# control.net
KiCad netlist of a schematic drawn in Altium Designer
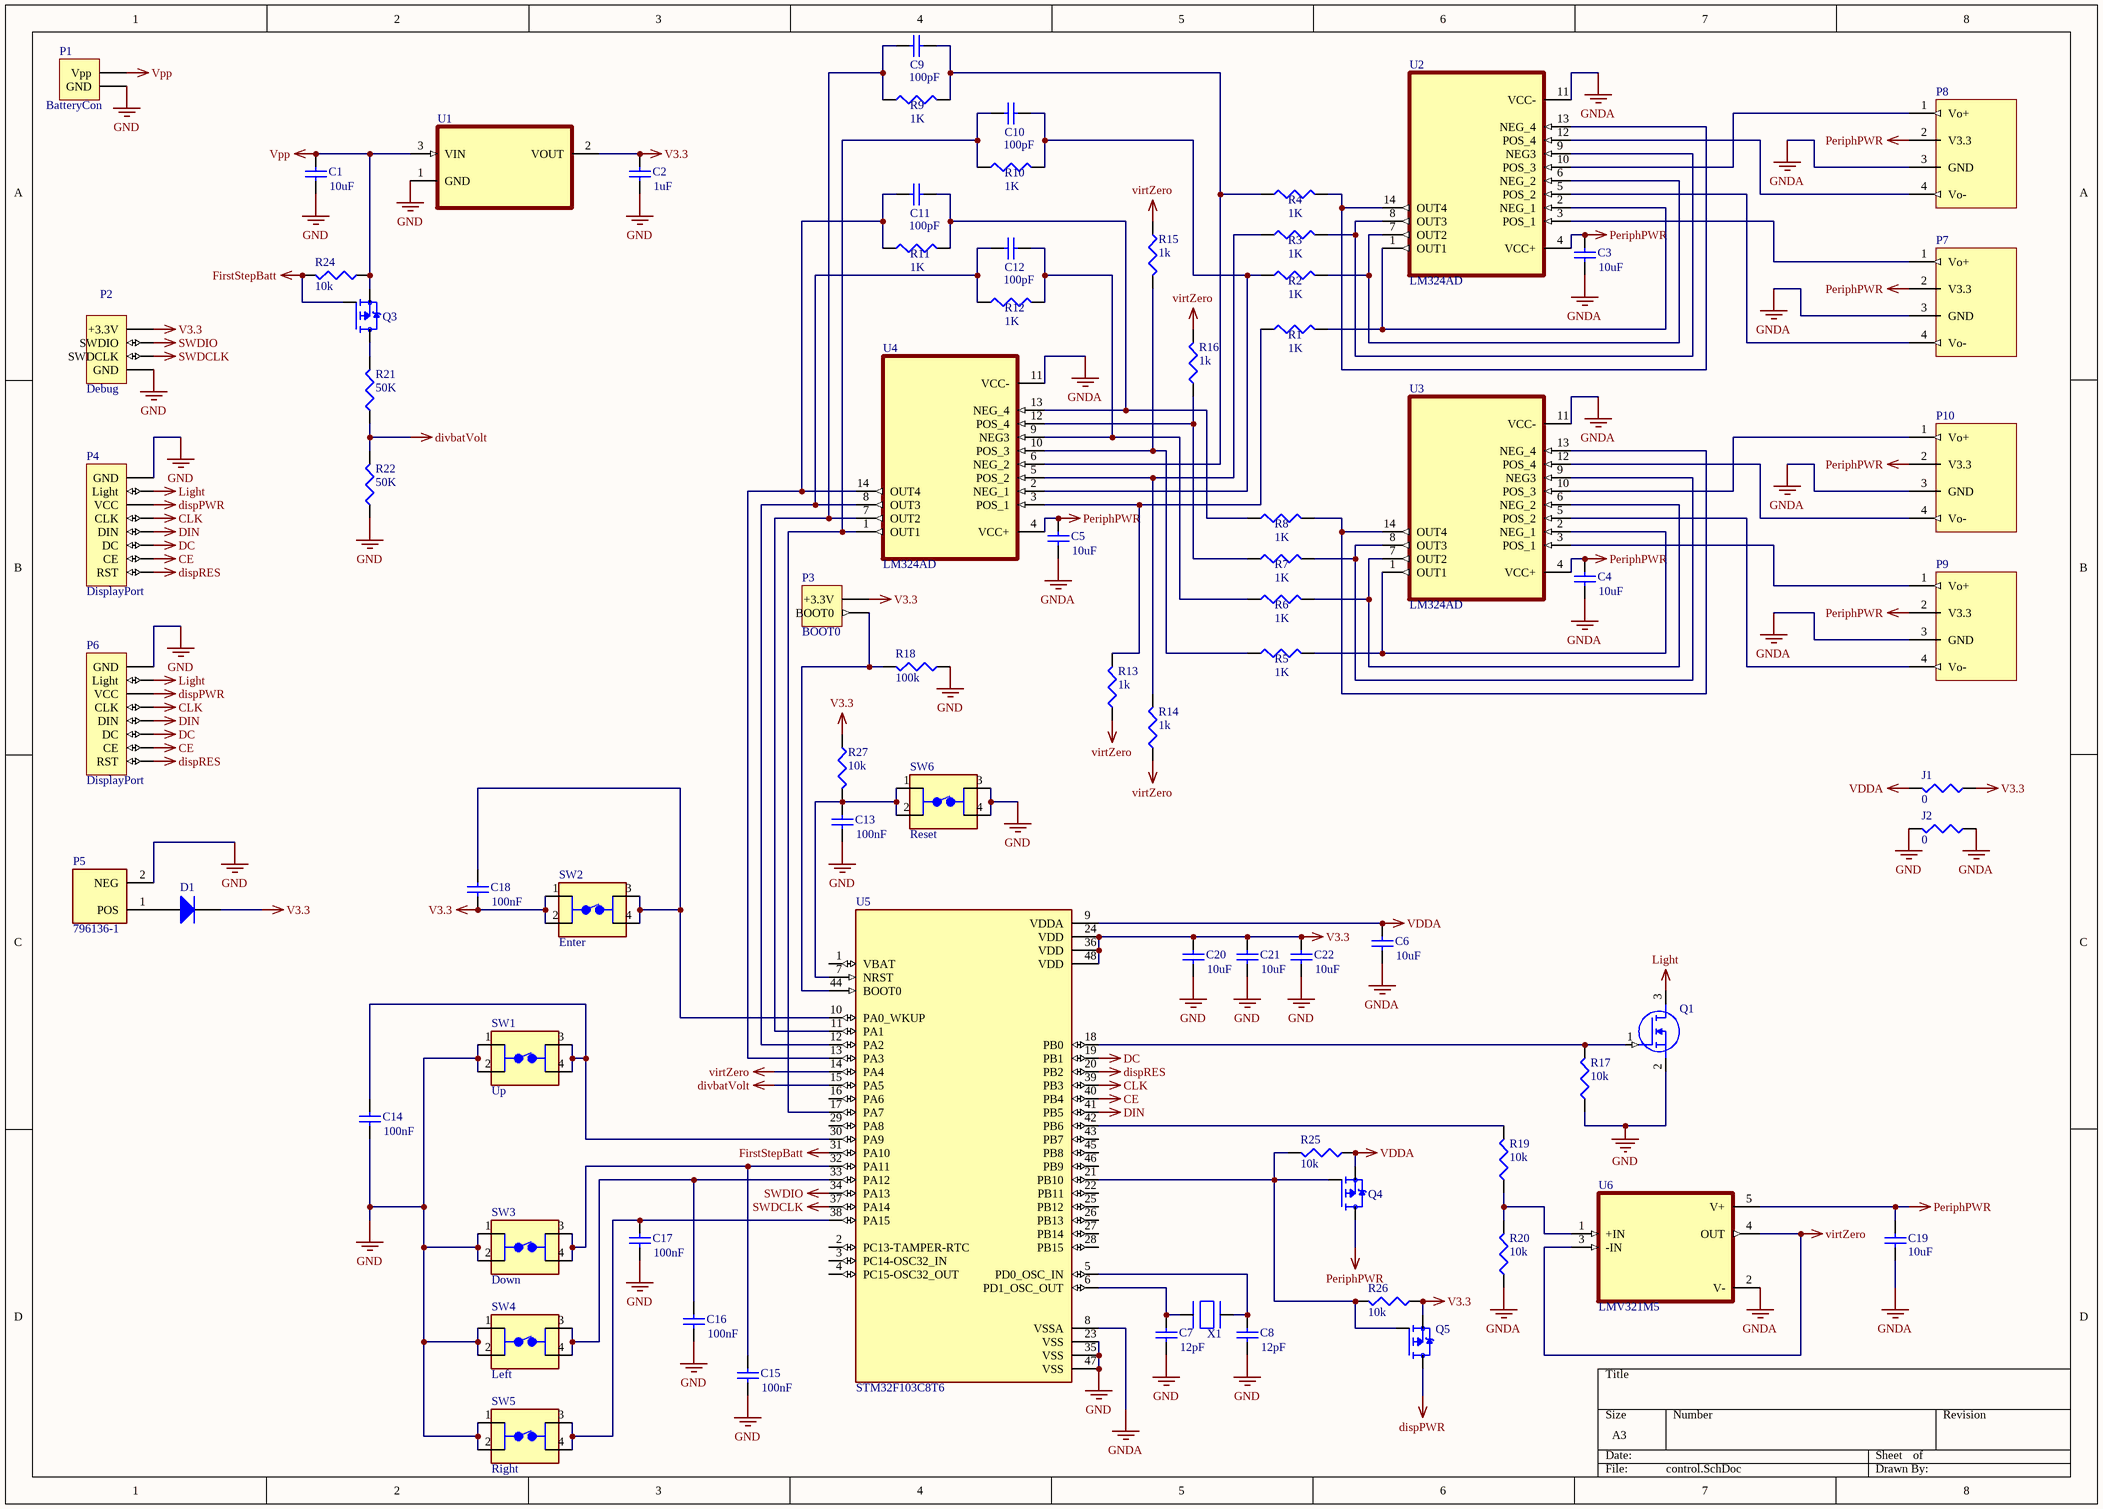
[diagram p0: control.SchDoc]

(export (version "E")
  (design (tool "Eeschema 10.0.6"))
  (components
    (comp (ref "C1")
      (value "10uF")
      (footprint "C1206")
      (description "Capacitor (Semiconductor SIM Model)")
      (fields (field (name "Comment") "Cap Semi") (field (name "PUBLISHER") "Altium Limited"))
      (libsource (lib "Miscellaneous Devices") (part "Cap Semi"))
    )
    (comp (ref "C2")
      (value "1uF")
      (footprint "C1206")
      (description "Capacitor (Semiconductor SIM Model)")
      (fields (field (name "Comment") "Cap Semi") (field (name "PUBLISHER") "Altium Limited"))
      (libsource (lib "Miscellaneous Devices") (part "Cap Semi"))
    )
    (comp (ref "C3")
      (value "10uF")
      (footprint "C1206")
      (description "Capacitor (Semiconductor SIM Model)")
      (fields (field (name "Comment") "Cap Semi") (field (name "PUBLISHER") "Altium Limited"))
      (libsource (lib "Miscellaneous Devices") (part "Cap Semi"))
    )
    (comp (ref "C4")
      (value "10uF")
      (footprint "C1206")
      (description "Capacitor (Semiconductor SIM Model)")
      (fields (field (name "Comment") "Cap Semi") (field (name "PUBLISHER") "Altium Limited"))
      (libsource (lib "Miscellaneous Devices") (part "Cap Semi"))
    )
    (comp (ref "C5")
      (value "10uF")
      (footprint "C1206")
      (description "Capacitor (Semiconductor SIM Model)")
      (fields (field (name "Comment") "Cap Semi") (field (name "PUBLISHER") "Altium Limited"))
      (libsource (lib "Miscellaneous Devices") (part "Cap Semi"))
    )
    (comp (ref "C6")
      (value "10uF")
      (footprint "C1206")
      (description "Capacitor (Semiconductor SIM Model)")
      (fields (field (name "Comment") "Cap Semi") (field (name "PUBLISHER") "Altium Limited"))
      (libsource (lib "Miscellaneous Devices") (part "Cap Semi"))
    )
    (comp (ref "C7")
      (value "12pF")
      (footprint "C1206")
      (description "Capacitor (Semiconductor SIM Model)")
      (fields (field (name "Comment") "Cap Semi") (field (name "PUBLISHER") "Altium Limited"))
      (libsource (lib "Miscellaneous Devices") (part "Cap Semi"))
    )
    (comp (ref "C8")
      (value "12pF")
      (footprint "C1206")
      (description "Capacitor (Semiconductor SIM Model)")
      (fields (field (name "Comment") "Cap Semi") (field (name "PUBLISHER") "Altium Limited"))
      (libsource (lib "Miscellaneous Devices") (part "Cap Semi"))
    )
    (comp (ref "C9")
      (value "100pF")
      (footprint "C1206")
      (description "Capacitor (Semiconductor SIM Model)")
      (fields (field (name "Comment") "Cap Semi") (field (name "PUBLISHER") "Altium Limited"))
      (libsource (lib "Miscellaneous Devices") (part "Cap Semi"))
    )
    (comp (ref "C10")
      (value "100pF")
      (footprint "C1206")
      (description "Capacitor (Semiconductor SIM Model)")
      (fields (field (name "Comment") "Cap Semi") (field (name "PUBLISHER") "Altium Limited"))
      (libsource (lib "Miscellaneous Devices") (part "Cap Semi"))
    )
    (comp (ref "C11")
      (value "100pF")
      (footprint "C1206")
      (description "Capacitor (Semiconductor SIM Model)")
      (fields (field (name "Comment") "Cap Semi") (field (name "PUBLISHER") "Altium Limited"))
      (libsource (lib "Miscellaneous Devices") (part "Cap Semi"))
    )
    (comp (ref "C12")
      (value "100pF")
      (footprint "C1206")
      (description "Capacitor (Semiconductor SIM Model)")
      (fields (field (name "Comment") "Cap Semi") (field (name "PUBLISHER") "Altium Limited"))
      (libsource (lib "Miscellaneous Devices") (part "Cap Semi"))
    )
    (comp (ref "C13")
      (value "100nF")
      (footprint "C1206")
      (description "Capacitor (Semiconductor SIM Model)")
      (fields (field (name "Comment") "Cap Semi") (field (name "PUBLISHER") "Altium Limited"))
      (libsource (lib "Miscellaneous Devices") (part "Cap Semi"))
    )
    (comp (ref "C14")
      (value "100nF")
      (footprint "C1206")
      (description "Capacitor (Semiconductor SIM Model)")
      (fields (field (name "Comment") "Cap Semi") (field (name "PUBLISHER") "Altium Limited"))
      (libsource (lib "Miscellaneous Devices") (part "Cap Semi"))
    )
    (comp (ref "C15")
      (value "100nF")
      (footprint "C1206")
      (description "Capacitor (Semiconductor SIM Model)")
      (fields (field (name "Comment") "Cap Semi") (field (name "PUBLISHER") "Altium Limited"))
      (libsource (lib "Miscellaneous Devices") (part "Cap Semi"))
    )
    (comp (ref "C16")
      (value "100nF")
      (footprint "C1206")
      (description "Capacitor (Semiconductor SIM Model)")
      (fields (field (name "Comment") "Cap Semi") (field (name "PUBLISHER") "Altium Limited"))
      (libsource (lib "Miscellaneous Devices") (part "Cap Semi"))
    )
    (comp (ref "C17")
      (value "100nF")
      (footprint "C1206")
      (description "Capacitor (Semiconductor SIM Model)")
      (fields (field (name "Comment") "Cap Semi") (field (name "PUBLISHER") "Altium Limited"))
      (libsource (lib "Miscellaneous Devices") (part "Cap Semi"))
    )
    (comp (ref "C18")
      (value "100nF")
      (footprint "C1206")
      (description "Capacitor (Semiconductor SIM Model)")
      (fields (field (name "Comment") "Cap Semi") (field (name "PUBLISHER") "Altium Limited"))
      (libsource (lib "Miscellaneous Devices") (part "Cap Semi"))
    )
    (comp (ref "C19")
      (value "10uF")
      (footprint "C1206")
      (description "Capacitor (Semiconductor SIM Model)")
      (fields (field (name "Comment") "Cap Semi") (field (name "PUBLISHER") "Altium Limited"))
      (libsource (lib "Miscellaneous Devices") (part "Cap Semi"))
    )
    (comp (ref "C20")
      (value "10uF")
      (footprint "C1206")
      (description "Capacitor (Semiconductor SIM Model)")
      (fields (field (name "Comment") "Cap Semi") (field (name "PUBLISHER") "Altium Limited"))
      (libsource (lib "Miscellaneous Devices") (part "Cap Semi"))
    )
    (comp (ref "C21")
      (value "10uF")
      (footprint "C1206")
      (description "Capacitor (Semiconductor SIM Model)")
      (fields (field (name "Comment") "Cap Semi") (field (name "PUBLISHER") "Altium Limited"))
      (libsource (lib "Miscellaneous Devices") (part "Cap Semi"))
    )
    (comp (ref "C22")
      (value "10uF")
      (footprint "C1206")
      (description "Capacitor (Semiconductor SIM Model)")
      (fields (field (name "Comment") "Cap Semi") (field (name "PUBLISHER") "Altium Limited"))
      (libsource (lib "Miscellaneous Devices") (part "Cap Semi"))
    )
    (comp (ref "D1")
      (value "Diode")
      (footprint "SMC")
      (description "Default Diode")
      (fields (field (name "PUBLISHER") "Altium Limited"))
      (libsource (lib "Miscellaneous Devices") (part "Diode"))
    )
    (comp (ref "J1")
      (value "0")
      (footprint "14-1210")
      (description "Resistor")
      (fields (field (name "Comment") "Res3") (field (name "PUBLISHER") "Altium Limited"))
      (libsource (lib "Miscellaneous Devices") (part "Res3"))
    )
    (comp (ref "J2")
      (value "0")
      (footprint "14-1210")
      (description "Resistor")
      (fields (field (name "Comment") "Res3") (field (name "PUBLISHER") "Altium Limited"))
      (libsource (lib "Miscellaneous Devices") (part "Res3"))
    )
    (comp (ref "P1")
      (value "BatteryCon")
      (footprint "HDR1X2")
      (description "Header, 2-Pin")
      (fields (field (name "PUBLISHER") "Altium Limited"))
      (libsource (lib "Miscellaneous Connectors") (part "Header 2"))
    )
    (comp (ref "P2")
      (value "Debug")
      (footprint "HDR1X4")
      (description "Header, 4-Pin")
      (fields (field (name "PUBLISHER") "Altium Limited"))
      (libsource (lib "Miscellaneous Connectors") (part "Header 4"))
    )
    (comp (ref "P3")
      (value "BOOT0")
      (footprint "HDR1X2")
      (description "Header, 2-Pin")
      (fields (field (name "PUBLISHER") "Altium Limited"))
      (libsource (lib "Miscellaneous Connectors") (part "Header 2"))
    )
    (comp (ref "P4")
      (value "DisplayPort")
      (footprint "HDR1X8")
      (description "Header, 8-Pin")
      (fields (field (name "PUBLISHER") "Altium Limited"))
      (libsource (lib "Miscellaneous Connectors") (part "Header 8"))
    )
    (comp (ref "P5")
      (value "796136-1")
      (footprint "TE_796136-1")
      (fields (field (name "MF") "TE Connectivity"))
      (libsource (lib "796136-1") (part "796136-1"))
    )
    (comp (ref "P6")
      (value "DisplayPort")
      (footprint "HDR1X8")
      (description "Header, 8-Pin")
      (fields (field (name "PUBLISHER") "Altium Limited"))
      (libsource (lib "Miscellaneous Connectors") (part "Header 8"))
    )
    (comp (ref "P7") (value "Conn") (footprint "ConnFoot") (libsource (lib "ConnLib") (part "ConnectorSMD")))
    (comp (ref "P8") (value "Conn") (footprint "ConnFoot") (libsource (lib "ConnLib") (part "ConnectorSMD")))
    (comp (ref "P9") (value "Conn") (footprint "ConnFoot") (libsource (lib "ConnLib") (part "ConnectorSMD")))
    (comp (ref "P10") (value "Conn") (footprint "ConnFoot") (libsource (lib "ConnLib") (part "ConnectorSMD")))
    (comp (ref "Q1")
      (value "IRLML0030TRPBF")
      (footprint "SOT23_L")
      (description "N-Channel 30V 5.3A _Ta_ 1.3W _Ta_ Surface Mount Micro3â„¢/SOT-23")
      (fields (field (name "MF") "Infineon Technologies"))
      (libsource (lib "IRLML0030TRPBF") (part "IRLML0030TRPBF"))
    )
    (comp (ref "Q3")
      (value "IRLML9301TRPBF")
      (footprint "SOT95P237X112-3N")
      (fields (field (name "MF") "Infineon Technologies"))
      (libsource (lib "IRLML9301TRPBF") (part "IRLML9301TRPBF"))
    )
    (comp (ref "Q4")
      (value "IRLML9301TRPBF")
      (footprint "SOT95P237X112-3N")
      (fields (field (name "MF") "Infineon Technologies"))
      (libsource (lib "IRLML9301TRPBF") (part "IRLML9301TRPBF"))
    )
    (comp (ref "Q5")
      (value "IRLML9301TRPBF")
      (footprint "SOT95P237X112-3N")
      (fields (field (name "MF") "Infineon Technologies"))
      (libsource (lib "IRLML9301TRPBF") (part "IRLML9301TRPBF"))
    )
    (comp (ref "R1")
      (value "1K")
      (footprint "14-1210")
      (description "Resistor")
      (fields (field (name "Comment") "Res3") (field (name "PUBLISHER") "Altium Limited"))
      (libsource (lib "Miscellaneous Devices") (part "Res3"))
    )
    (comp (ref "R2")
      (value "1K")
      (footprint "14-1210")
      (description "Resistor")
      (fields (field (name "Comment") "Res3") (field (name "PUBLISHER") "Altium Limited"))
      (libsource (lib "Miscellaneous Devices") (part "Res3"))
    )
    (comp (ref "R3")
      (value "1K")
      (footprint "14-1210")
      (description "Resistor")
      (fields (field (name "Comment") "Res3") (field (name "PUBLISHER") "Altium Limited"))
      (libsource (lib "Miscellaneous Devices") (part "Res3"))
    )
    (comp (ref "R4")
      (value "1K")
      (footprint "14-1210")
      (description "Resistor")
      (fields (field (name "Comment") "Res3") (field (name "PUBLISHER") "Altium Limited"))
      (libsource (lib "Miscellaneous Devices") (part "Res3"))
    )
    (comp (ref "R5")
      (value "1K")
      (footprint "14-1210")
      (description "Resistor")
      (fields (field (name "Comment") "Res3") (field (name "PUBLISHER") "Altium Limited"))
      (libsource (lib "Miscellaneous Devices") (part "Res3"))
    )
    (comp (ref "R6")
      (value "1K")
      (footprint "14-1210")
      (description "Resistor")
      (fields (field (name "Comment") "Res3") (field (name "PUBLISHER") "Altium Limited"))
      (libsource (lib "Miscellaneous Devices") (part "Res3"))
    )
    (comp (ref "R7")
      (value "1K")
      (footprint "14-1210")
      (description "Resistor")
      (fields (field (name "Comment") "Res3") (field (name "PUBLISHER") "Altium Limited"))
      (libsource (lib "Miscellaneous Devices") (part "Res3"))
    )
    (comp (ref "R8")
      (value "1K")
      (footprint "14-1210")
      (description "Resistor")
      (fields (field (name "Comment") "Res3") (field (name "PUBLISHER") "Altium Limited"))
      (libsource (lib "Miscellaneous Devices") (part "Res3"))
    )
    (comp (ref "R9")
      (value "1K")
      (footprint "14-1210")
      (description "Resistor")
      (fields (field (name "Comment") "Res3") (field (name "PUBLISHER") "Altium Limited"))
      (libsource (lib "Miscellaneous Devices") (part "Res3"))
    )
    (comp (ref "R10")
      (value "1K")
      (footprint "14-1210")
      (description "Resistor")
      (fields (field (name "Comment") "Res3") (field (name "PUBLISHER") "Altium Limited"))
      (libsource (lib "Miscellaneous Devices") (part "Res3"))
    )
    (comp (ref "R11")
      (value "1K")
      (footprint "14-1210")
      (description "Resistor")
      (fields (field (name "Comment") "Res3") (field (name "PUBLISHER") "Altium Limited"))
      (libsource (lib "Miscellaneous Devices") (part "Res3"))
    )
    (comp (ref "R12")
      (value "1K")
      (footprint "14-1210")
      (description "Resistor")
      (fields (field (name "Comment") "Res3") (field (name "PUBLISHER") "Altium Limited"))
      (libsource (lib "Miscellaneous Devices") (part "Res3"))
    )
    (comp (ref "R13")
      (value "1k")
      (footprint "14-1210")
      (description "Resistor")
      (fields (field (name "Comment") "Res3") (field (name "PUBLISHER") "Altium Limited"))
      (libsource (lib "Miscellaneous Devices") (part "Res3"))
    )
    (comp (ref "R14")
      (value "1k")
      (footprint "14-1210")
      (description "Resistor")
      (fields (field (name "Comment") "Res3") (field (name "PUBLISHER") "Altium Limited"))
      (libsource (lib "Miscellaneous Devices") (part "Res3"))
    )
    (comp (ref "R15")
      (value "1k")
      (footprint "14-1210")
      (description "Resistor")
      (fields (field (name "Comment") "Res3") (field (name "PUBLISHER") "Altium Limited"))
      (libsource (lib "Miscellaneous Devices") (part "Res3"))
    )
    (comp (ref "R16")
      (value "1k")
      (footprint "14-1210")
      (description "Resistor")
      (fields (field (name "Comment") "Res3") (field (name "PUBLISHER") "Altium Limited"))
      (libsource (lib "Miscellaneous Devices") (part "Res3"))
    )
    (comp (ref "R17")
      (value "10k")
      (footprint "14-1210")
      (description "Resistor")
      (fields (field (name "Comment") "Res3") (field (name "PUBLISHER") "Altium Limited"))
      (libsource (lib "Miscellaneous Devices") (part "Res3"))
    )
    (comp (ref "R18")
      (value "100k")
      (footprint "14-1210")
      (description "Resistor")
      (fields (field (name "Comment") "Res3") (field (name "PUBLISHER") "Altium Limited"))
      (libsource (lib "Miscellaneous Devices") (part "Res3"))
    )
    (comp (ref "R19")
      (value "10k")
      (footprint "14-1210")
      (description "Resistor")
      (fields (field (name "Comment") "Res3") (field (name "PUBLISHER") "Altium Limited"))
      (libsource (lib "Miscellaneous Devices") (part "Res3"))
    )
    (comp (ref "R20")
      (value "10k")
      (footprint "14-1210")
      (description "Resistor")
      (fields (field (name "Comment") "Res3") (field (name "PUBLISHER") "Altium Limited"))
      (libsource (lib "Miscellaneous Devices") (part "Res3"))
    )
    (comp (ref "R21")
      (value "50K")
      (footprint "14-1210")
      (description "Resistor")
      (fields (field (name "Comment") "Res3") (field (name "PUBLISHER") "Altium Limited"))
      (libsource (lib "Miscellaneous Devices") (part "Res3"))
    )
    (comp (ref "R22")
      (value "50K")
      (footprint "14-1210")
      (description "Resistor")
      (fields (field (name "Comment") "Res3") (field (name "PUBLISHER") "Altium Limited"))
      (libsource (lib "Miscellaneous Devices") (part "Res3"))
    )
    (comp (ref "R24")
      (value "10k")
      (footprint "14-1210")
      (description "Resistor")
      (fields (field (name "Comment") "Res3") (field (name "PUBLISHER") "Altium Limited"))
      (libsource (lib "Miscellaneous Devices") (part "Res3"))
    )
    (comp (ref "R25")
      (value "10k")
      (footprint "14-1210")
      (description "Resistor")
      (fields (field (name "Comment") "Res3") (field (name "PUBLISHER") "Altium Limited"))
      (libsource (lib "Miscellaneous Devices") (part "Res3"))
    )
    (comp (ref "R26")
      (value "10k")
      (footprint "14-1210")
      (description "Resistor")
      (fields (field (name "Comment") "Res3") (field (name "PUBLISHER") "Altium Limited"))
      (libsource (lib "Miscellaneous Devices") (part "Res3"))
    )
    (comp (ref "R27")
      (value "10k")
      (footprint "14-1210")
      (description "Resistor")
      (fields (field (name "Comment") "Res3") (field (name "PUBLISHER") "Altium Limited"))
      (libsource (lib "Miscellaneous Devices") (part "Res3"))
    )
    (comp (ref "SW1")
      (value "Up")
      (footprint "SnapEDApcb:TE_FSM4JSMA")
      (description "Tactile Switch SPST-NO Top Actuated Surface Mount")
      (fields (field (name "MP") "FSM4JSMA") (field (name "MF") "TE Connectivity"))
      (libsource (lib "FSM4JSMA") (part "FSM4JSMA"))
    )
    (comp (ref "SW2")
      (value "Enter")
      (footprint "TE_FSM4JSMA")
      (description "Tactile Switch SPST-NO Top Actuated Surface Mount")
      (fields (field (name "MP") "FSM4JSMA") (field (name "MF") "TE Connectivity"))
      (libsource (lib "FSM4JSMA") (part "FSM4JSMA"))
    )
    (comp (ref "SW3")
      (value "Down")
      (footprint "SnapEDApcb:TE_FSM4JSMA")
      (description "Tactile Switch SPST-NO Top Actuated Surface Mount")
      (fields (field (name "MP") "FSM4JSMA") (field (name "MF") "TE Connectivity"))
      (libsource (lib "FSM4JSMA") (part "FSM4JSMA"))
    )
    (comp (ref "SW4")
      (value "Left")
      (footprint "SnapEDApcb:TE_FSM4JSMA")
      (description "Tactile Switch SPST-NO Top Actuated Surface Mount")
      (fields (field (name "MP") "FSM4JSMA") (field (name "MF") "TE Connectivity"))
      (libsource (lib "FSM4JSMA") (part "FSM4JSMA"))
    )
    (comp (ref "SW5")
      (value "Right")
      (footprint "SnapEDApcb:TE_FSM4JSMA")
      (description "Tactile Switch SPST-NO Top Actuated Surface Mount")
      (fields (field (name "MP") "FSM4JSMA") (field (name "MF") "TE Connectivity"))
      (libsource (lib "FSM4JSMA") (part "FSM4JSMA"))
    )
    (comp (ref "SW6")
      (value "Reset")
      (footprint "TE_FSM4JSMA")
      (description "Tactile Switch SPST-NO Top Actuated Surface Mount")
      (fields (field (name "MP") "FSM4JSMA") (field (name "MF") "TE Connectivity"))
      (libsource (lib "FSM4JSMA") (part "FSM4JSMA"))
    )
    (comp (ref "U1")
      (value "MCP1702T-3302E/CB")
      (footprint "SOT95P255X145-3N:SOT95P255X145-3N")
      (description "Linear Voltage Regulator IC Positive Fixed 1 Output 250mA SOT-23A-3")
      (fields (field (name "MF") "Microchip Technology"))
      (libsource (lib "MCP1702T-3302E_CB") (part "MCP1702T-3302E/CB"))
    )
    (comp (ref "U2")
      (value "LM324AD")
      (footprint "SOIC127P600X175-14N")
      (description "Op Amp Quad Low Power Amplifier Â±15V/30V 14-Pin SOIC Tube")
      (fields (field (name "MF") "Texas Instruments"))
      (libsource (lib "LM324AD") (part "LM324AD"))
    )
    (comp (ref "U3")
      (value "LM324AD")
      (footprint "SOIC127P600X175-14N")
      (description "Op Amp Quad Low Power Amplifier Â±15V/30V 14-Pin SOIC Tube")
      (fields (field (name "MF") "Texas Instruments"))
      (libsource (lib "LM324AD") (part "LM324AD"))
    )
    (comp (ref "U4")
      (value "LM324AD")
      (footprint "SOIC127P600X175-14N")
      (description "Op Amp Quad Low Power Amplifier Â±15V/30V 14-Pin SOIC Tube")
      (fields (field (name "MF") "Texas Instruments"))
      (libsource (lib "LM324AD") (part "LM324AD"))
    )
    (comp (ref "U5")
      (value "STM32F103C8T6")
      (footprint "QFP50P900X900X160-48N")
      (description "ARMÂ® CortexÂ®-M3 STM32F1 Microcontroller IC 32-Bit 72MHz 64KB _64K x 8_ FLASH")
      (fields (field (name "MF") "STMicroelectronics"))
      (libsource (lib "STM32F103C8T6") (part "STM32F103C8T6"))
    )
    (comp (ref "U6")
      (value "LMV321M5")
      (footprint "SOT95P280X145-5N")
      (fields (field (name "MP") "LMV321M5/NOPB") (field (name "MF") "Texas Instruments"))
      (libsource (lib "LMV321M5") (part "LMV321M5"))
    )
    (comp (ref "X1")
      (value "ABLS-8.000MHZ-B4-T")
      (footprint "HC-49/US")
      (description "8MHz Â±30ppm Crystal 18pF 80 Ohms HC-49/US")
      (fields (field (name "MF") "Abracon LLC"))
      (libsource (lib "ABLS-8.000MHZ-B4-T") (part "ABLS-8.000MHZ-B4-T"))
    )
  )
  (nets
    (net (code "1") (name "CE") (class "Default")
      (node (ref "P4") (pin "2") (pinfunction "CE_2") (pintype "bidirectional"))
      (node (ref "P6") (pin "2") (pinfunction "CE_2") (pintype "bidirectional"))
      (node (ref "U5") (pin "40") (pinfunction "PB4_40") (pintype "bidirectional"))
    )
    (net (code "2") (name "CLK") (class "Default")
      (node (ref "P4") (pin "5") (pinfunction "CLK_5") (pintype "bidirectional"))
      (node (ref "P6") (pin "5") (pinfunction "CLK_5") (pintype "bidirectional"))
      (node (ref "U5") (pin "39") (pinfunction "PB3_39") (pintype "bidirectional"))
    )
    (net (code "3") (name "DC") (class "Default")
      (node (ref "P4") (pin "3") (pinfunction "DC_3") (pintype "bidirectional"))
      (node (ref "P6") (pin "3") (pinfunction "DC_3") (pintype "bidirectional"))
      (node (ref "U5") (pin "19") (pinfunction "PB1_19") (pintype "bidirectional"))
    )
    (net (code "4") (name "DIN") (class "Default")
      (node (ref "P4") (pin "4") (pinfunction "DIN_4") (pintype "bidirectional"))
      (node (ref "P6") (pin "4") (pinfunction "DIN_4") (pintype "bidirectional"))
      (node (ref "U5") (pin "41") (pinfunction "PB5_41") (pintype "bidirectional"))
    )
    (net (code "5") (name "FirstStepBatt") (class "Default")
      (node (ref "Q3") (pin "1") (pinfunction "G_1") (pintype "passive"))
      (node (ref "R24") (pin "2") (pinfunction "2_2") (pintype "passive"))
      (node (ref "U5") (pin "31") (pinfunction "PA10_31") (pintype "bidirectional"))
    )
    (net (code "6") (name "GND") (class "Default")
      (node (ref "C1") (pin "1") (pinfunction "1_1") (pintype "passive"))
      (node (ref "C13") (pin "1") (pinfunction "1_1") (pintype "passive"))
      (node (ref "C14") (pin "1") (pinfunction "1_1") (pintype "passive"))
      (node (ref "C15") (pin "1") (pinfunction "1_1") (pintype "passive"))
      (node (ref "C16") (pin "1") (pinfunction "1_1") (pintype "passive"))
      (node (ref "C17") (pin "1") (pinfunction "1_1") (pintype "passive"))
      (node (ref "C2") (pin "1") (pinfunction "1_1") (pintype "passive"))
      (node (ref "C20") (pin "1") (pinfunction "1_1") (pintype "passive"))
      (node (ref "C21") (pin "1") (pinfunction "1_1") (pintype "passive"))
      (node (ref "C22") (pin "1") (pinfunction "1_1") (pintype "passive"))
      (node (ref "C7") (pin "1") (pinfunction "1_1") (pintype "passive"))
      (node (ref "C8") (pin "1") (pinfunction "1_1") (pintype "passive"))
      (node (ref "J2") (pin "2") (pinfunction "2_2") (pintype "passive"))
      (node (ref "P1") (pin "1") (pinfunction "GND_1") (pintype "power_in"))
      (node (ref "P2") (pin "1") (pinfunction "GND_1") (pintype "power_in"))
      (node (ref "P4") (pin "8") (pinfunction "GND_8") (pintype "power_in"))
      (node (ref "P5") (pin "2") (pinfunction "NEG_2") (pintype "passive"))
      (node (ref "P6") (pin "8") (pinfunction "GND_8") (pintype "power_in"))
      (node (ref "Q1") (pin "2") (pinfunction "S_2") (pintype "bidirectional"))
      (node (ref "R17") (pin "1") (pinfunction "1_1") (pintype "passive"))
      (node (ref "R18") (pin "1") (pinfunction "1_1") (pintype "passive"))
      (node (ref "R22") (pin "1") (pinfunction "1_1") (pintype "passive"))
      (node (ref "SW1") (pin "1") (pinfunction "1_1") (pintype "passive"))
      (node (ref "SW1") (pin "2") (pinfunction "2_2") (pintype "passive"))
      (node (ref "SW3") (pin "1") (pinfunction "1_1") (pintype "passive"))
      (node (ref "SW3") (pin "2") (pinfunction "2_2") (pintype "passive"))
      (node (ref "SW4") (pin "1") (pinfunction "1_1") (pintype "passive"))
      (node (ref "SW4") (pin "2") (pinfunction "2_2") (pintype "passive"))
      (node (ref "SW5") (pin "1") (pinfunction "1_1") (pintype "passive"))
      (node (ref "SW5") (pin "2") (pinfunction "2_2") (pintype "passive"))
      (node (ref "SW6") (pin "3") (pinfunction "3_3") (pintype "passive"))
      (node (ref "SW6") (pin "4") (pinfunction "4_4") (pintype "passive"))
      (node (ref "U1") (pin "1") (pinfunction "GND_1") (pintype "passive"))
      (node (ref "U5") (pin "23") (pinfunction "VSS_23") (pintype "power_in"))
      (node (ref "U5") (pin "35") (pinfunction "VSS_35") (pintype "power_in"))
      (node (ref "U5") (pin "47") (pinfunction "VSS_47") (pintype "power_in"))
    )
    (net (code "7") (name "GNDA") (class "Default")
      (node (ref "C19") (pin "2") (pinfunction "2_2") (pintype "passive"))
      (node (ref "C3") (pin "1") (pinfunction "1_1") (pintype "passive"))
      (node (ref "C4") (pin "1") (pinfunction "1_1") (pintype "passive"))
      (node (ref "C5") (pin "1") (pinfunction "1_1") (pintype "passive"))
      (node (ref "C6") (pin "1") (pinfunction "1_1") (pintype "passive"))
      (node (ref "J2") (pin "1") (pinfunction "1_1") (pintype "passive"))
      (node (ref "P10") (pin "3") (pinfunction "GND_3") (pintype "power_in"))
      (node (ref "P7") (pin "3") (pinfunction "GND_3") (pintype "power_in"))
      (node (ref "P8") (pin "3") (pinfunction "GND_3") (pintype "power_in"))
      (node (ref "P9") (pin "3") (pinfunction "GND_3") (pintype "power_in"))
      (node (ref "R20") (pin "1") (pinfunction "1_1") (pintype "passive"))
      (node (ref "U2") (pin "11") (pinfunction "VCC-_11") (pintype "power_in"))
      (node (ref "U3") (pin "11") (pinfunction "VCC-_11") (pintype "power_in"))
      (node (ref "U4") (pin "11") (pinfunction "VCC-_11") (pintype "power_in"))
      (node (ref "U5") (pin "8") (pinfunction "VSSA_8") (pintype "power_in"))
      (node (ref "U6") (pin "2") (pinfunction "V-_2") (pintype "power_in"))
    )
    (net (code "8") (name "Light") (class "Default")
      (node (ref "P4") (pin "7") (pinfunction "Light_7") (pintype "bidirectional"))
      (node (ref "P6") (pin "7") (pinfunction "Light_7") (pintype "bidirectional"))
      (node (ref "Q1") (pin "3") (pinfunction "D_3") (pintype "bidirectional"))
    )
    (net (code "9") (name "Net-(D1-A)") (class "Default")
      (node (ref "D1") (pin "1") (pinfunction "A_1") (pintype "passive"))
      (node (ref "P5") (pin "1") (pinfunction "POS_1") (pintype "passive"))
    )
    (net (code "10") (name "Net-(P3-GND)") (class "Default")
      (node (ref "P3") (pin "1") (pinfunction "GND_1") (pintype "power_in"))
      (node (ref "R18") (pin "2") (pinfunction "2_2") (pintype "passive"))
      (node (ref "U5") (pin "44") (pinfunction "BOOT0_44") (pintype "input"))
    )
    (net (code "11") (name "Net-(P7-Vo+)") (class "Default")
      (node (ref "P7") (pin "1") (pinfunction "Vo+_1") (pintype "output"))
      (node (ref "U2") (pin "3") (pinfunction "POS_1_3") (pintype "input"))
    )
    (net (code "12") (name "Net-(P7-Vo-)") (class "Default")
      (node (ref "P7") (pin "4") (pinfunction "Vo-_4") (pintype "output"))
      (node (ref "U2") (pin "5") (pinfunction "POS_2_5") (pintype "input"))
    )
    (net (code "13") (name "Net-(P8-Vo+)") (class "Default")
      (node (ref "P8") (pin "1") (pinfunction "Vo+_1") (pintype "output"))
      (node (ref "U2") (pin "10") (pinfunction "POS_3_10") (pintype "input"))
    )
    (net (code "14") (name "Net-(P8-Vo-)") (class "Default")
      (node (ref "P8") (pin "4") (pinfunction "Vo-_4") (pintype "output"))
      (node (ref "U2") (pin "12") (pinfunction "POS_4_12") (pintype "input"))
    )
    (net (code "15") (name "Net-(P9-Vo+)") (class "Default")
      (node (ref "P9") (pin "1") (pinfunction "Vo+_1") (pintype "output"))
      (node (ref "U3") (pin "3") (pinfunction "POS_1_3") (pintype "input"))
    )
    (net (code "16") (name "Net-(P9-Vo-)") (class "Default")
      (node (ref "P9") (pin "4") (pinfunction "Vo-_4") (pintype "output"))
      (node (ref "U3") (pin "5") (pinfunction "POS_2_5") (pintype "input"))
    )
    (net (code "17") (name "Net-(P10-Vo+)") (class "Default")
      (node (ref "P10") (pin "1") (pinfunction "Vo+_1") (pintype "output"))
      (node (ref "U3") (pin "10") (pinfunction "POS_3_10") (pintype "input"))
    )
    (net (code "18") (name "Net-(P10-Vo-)") (class "Default")
      (node (ref "P10") (pin "4") (pinfunction "Vo-_4") (pintype "output"))
      (node (ref "U3") (pin "12") (pinfunction "POS_4_12") (pintype "input"))
    )
    (net (code "19") (name "Net-(Q1-G)") (class "Default")
      (node (ref "Q1") (pin "1") (pinfunction "G_1") (pintype "input"))
      (node (ref "R17") (pin "2") (pinfunction "2_2") (pintype "passive"))
      (node (ref "U5") (pin "18") (pinfunction "PB0_18") (pintype "bidirectional"))
    )
    (net (code "20") (name "Net-(Q3-D)") (class "Default")
      (node (ref "Q3") (pin "3") (pinfunction "D_3") (pintype "passive"))
      (node (ref "R21") (pin "2") (pinfunction "2_2") (pintype "passive"))
    )
    (net (code "21") (name "Net-(Q4-G)") (class "Default")
      (node (ref "Q4") (pin "1") (pinfunction "G_1") (pintype "passive"))
      (node (ref "Q5") (pin "1") (pinfunction "G_1") (pintype "passive"))
      (node (ref "R25") (pin "2") (pinfunction "2_2") (pintype "passive"))
      (node (ref "R26") (pin "2") (pinfunction "2_2") (pintype "passive"))
      (node (ref "U5") (pin "21") (pinfunction "PB10_21") (pintype "bidirectional"))
    )
    (net (code "22") (name "Net-(U2-NEG3)") (class "Default")
      (node (ref "R3") (pin "2") (pinfunction "2_2") (pintype "passive"))
      (node (ref "U2") (pin "8") (pinfunction "OUT3_8") (pintype "output"))
      (node (ref "U2") (pin "9") (pinfunction "NEG3_9") (pintype "input"))
    )
    (net (code "23") (name "Net-(U2-NEG_1)") (class "Default")
      (node (ref "R1") (pin "2") (pinfunction "2_2") (pintype "passive"))
      (node (ref "U2") (pin "1") (pinfunction "OUT1_1") (pintype "output"))
      (node (ref "U2") (pin "2") (pinfunction "NEG_1_2") (pintype "input"))
    )
    (net (code "24") (name "Net-(U2-NEG_2)") (class "Default")
      (node (ref "R2") (pin "2") (pinfunction "2_2") (pintype "passive"))
      (node (ref "U2") (pin "6") (pinfunction "NEG_2_6") (pintype "input"))
      (node (ref "U2") (pin "7") (pinfunction "OUT2_7") (pintype "output"))
    )
    (net (code "25") (name "Net-(U2-NEG_4)") (class "Default")
      (node (ref "R4") (pin "2") (pinfunction "2_2") (pintype "passive"))
      (node (ref "U2") (pin "13") (pinfunction "NEG_4_13") (pintype "input"))
      (node (ref "U2") (pin "14") (pinfunction "OUT4_14") (pintype "output"))
    )
    (net (code "26") (name "Net-(U3-NEG3)") (class "Default")
      (node (ref "R7") (pin "2") (pinfunction "2_2") (pintype "passive"))
      (node (ref "U3") (pin "8") (pinfunction "OUT3_8") (pintype "output"))
      (node (ref "U3") (pin "9") (pinfunction "NEG3_9") (pintype "input"))
    )
    (net (code "27") (name "Net-(U3-NEG_1)") (class "Default")
      (node (ref "R5") (pin "2") (pinfunction "2_2") (pintype "passive"))
      (node (ref "U3") (pin "1") (pinfunction "OUT1_1") (pintype "output"))
      (node (ref "U3") (pin "2") (pinfunction "NEG_1_2") (pintype "input"))
    )
    (net (code "28") (name "Net-(U3-NEG_2)") (class "Default")
      (node (ref "R6") (pin "2") (pinfunction "2_2") (pintype "passive"))
      (node (ref "U3") (pin "6") (pinfunction "NEG_2_6") (pintype "input"))
      (node (ref "U3") (pin "7") (pinfunction "OUT2_7") (pintype "output"))
    )
    (net (code "29") (name "Net-(U3-NEG_4)") (class "Default")
      (node (ref "R8") (pin "2") (pinfunction "2_2") (pintype "passive"))
      (node (ref "U3") (pin "13") (pinfunction "NEG_4_13") (pintype "input"))
      (node (ref "U3") (pin "14") (pinfunction "OUT4_14") (pintype "output"))
    )
    (net (code "30") (name "Net-(U4-NEG3)") (class "Default")
      (node (ref "C12") (pin "2") (pinfunction "2_2") (pintype "passive"))
      (node (ref "R12") (pin "2") (pinfunction "2_2") (pintype "passive"))
      (node (ref "R6") (pin "1") (pinfunction "1_1") (pintype "passive"))
      (node (ref "U4") (pin "9") (pinfunction "NEG3_9") (pintype "input"))
    )
    (net (code "31") (name "Net-(U4-NEG_1)") (class "Default")
      (node (ref "C10") (pin "2") (pinfunction "2_2") (pintype "passive"))
      (node (ref "R10") (pin "2") (pinfunction "2_2") (pintype "passive"))
      (node (ref "R2") (pin "1") (pinfunction "1_1") (pintype "passive"))
      (node (ref "U4") (pin "2") (pinfunction "NEG_1_2") (pintype "input"))
    )
    (net (code "32") (name "Net-(U4-NEG_2)") (class "Default")
      (node (ref "C9") (pin "2") (pinfunction "2_2") (pintype "passive"))
      (node (ref "R4") (pin "1") (pinfunction "1_1") (pintype "passive"))
      (node (ref "R9") (pin "2") (pinfunction "2_2") (pintype "passive"))
      (node (ref "U4") (pin "6") (pinfunction "NEG_2_6") (pintype "input"))
    )
    (net (code "33") (name "Net-(U4-NEG_4)") (class "Default")
      (node (ref "C11") (pin "2") (pinfunction "2_2") (pintype "passive"))
      (node (ref "R11") (pin "2") (pinfunction "2_2") (pintype "passive"))
      (node (ref "R8") (pin "1") (pinfunction "1_1") (pintype "passive"))
      (node (ref "U4") (pin "13") (pinfunction "NEG_4_13") (pintype "input"))
    )
    (net (code "34") (name "Net-(U4-OUT1)") (class "Default")
      (node (ref "C10") (pin "1") (pinfunction "1_1") (pintype "passive"))
      (node (ref "R10") (pin "1") (pinfunction "1_1") (pintype "passive"))
      (node (ref "U4") (pin "1") (pinfunction "OUT1_1") (pintype "output"))
      (node (ref "U5") (pin "17") (pinfunction "PA7_17") (pintype "bidirectional"))
    )
    (net (code "35") (name "Net-(U4-OUT2)") (class "Default")
      (node (ref "C9") (pin "1") (pinfunction "1_1") (pintype "passive"))
      (node (ref "R9") (pin "1") (pinfunction "1_1") (pintype "passive"))
      (node (ref "U4") (pin "7") (pinfunction "OUT2_7") (pintype "output"))
      (node (ref "U5") (pin "11") (pinfunction "PA1_11") (pintype "bidirectional"))
    )
    (net (code "36") (name "Net-(U4-OUT3)") (class "Default")
      (node (ref "C12") (pin "1") (pinfunction "1_1") (pintype "passive"))
      (node (ref "R12") (pin "1") (pinfunction "1_1") (pintype "passive"))
      (node (ref "U4") (pin "8") (pinfunction "OUT3_8") (pintype "output"))
      (node (ref "U5") (pin "12") (pinfunction "PA2_12") (pintype "bidirectional"))
    )
    (net (code "37") (name "Net-(U4-OUT4)") (class "Default")
      (node (ref "C11") (pin "1") (pinfunction "1_1") (pintype "passive"))
      (node (ref "R11") (pin "1") (pinfunction "1_1") (pintype "passive"))
      (node (ref "U4") (pin "14") (pinfunction "OUT4_14") (pintype "output"))
      (node (ref "U5") (pin "13") (pinfunction "PA3_13") (pintype "bidirectional"))
    )
    (net (code "38") (name "Net-(U4-POS_1)") (class "Default")
      (node (ref "R1") (pin "1") (pinfunction "1_1") (pintype "passive"))
      (node (ref "R13") (pin "2") (pinfunction "2_2") (pintype "passive"))
      (node (ref "U4") (pin "3") (pinfunction "POS_1_3") (pintype "input"))
    )
    (net (code "39") (name "Net-(U4-POS_2)") (class "Default")
      (node (ref "R14") (pin "2") (pinfunction "2_2") (pintype "passive"))
      (node (ref "R3") (pin "1") (pinfunction "1_1") (pintype "passive"))
      (node (ref "U4") (pin "5") (pinfunction "POS_2_5") (pintype "input"))
    )
    (net (code "40") (name "Net-(U4-POS_3)") (class "Default")
      (node (ref "R15") (pin "2") (pinfunction "2_2") (pintype "passive"))
      (node (ref "R5") (pin "1") (pinfunction "1_1") (pintype "passive"))
      (node (ref "U4") (pin "10") (pinfunction "POS_3_10") (pintype "input"))
    )
    (net (code "41") (name "Net-(U4-POS_4)") (class "Default")
      (node (ref "R16") (pin "1") (pinfunction "1_1") (pintype "passive"))
      (node (ref "R7") (pin "1") (pinfunction "1_1") (pintype "passive"))
      (node (ref "U4") (pin "12") (pinfunction "POS_4_12") (pintype "input"))
    )
    (net (code "42") (name "Net-(U5-NRST)") (class "Default")
      (node (ref "C13") (pin "2") (pinfunction "2_2") (pintype "passive"))
      (node (ref "R27") (pin "2") (pinfunction "2_2") (pintype "passive"))
      (node (ref "SW6") (pin "1") (pinfunction "1_1") (pintype "passive"))
      (node (ref "SW6") (pin "2") (pinfunction "2_2") (pintype "passive"))
      (node (ref "U5") (pin "7") (pinfunction "NRST_7") (pintype "input"))
    )
    (net (code "43") (name "Net-(U5-PA0_WKUP)") (class "Default")
      (node (ref "C18") (pin "2") (pinfunction "2_2") (pintype "passive"))
      (node (ref "SW2") (pin "3") (pinfunction "3_3") (pintype "passive"))
      (node (ref "SW2") (pin "4") (pinfunction "4_4") (pintype "passive"))
      (node (ref "U5") (pin "10") (pinfunction "PA0_WKUP_10") (pintype "bidirectional"))
    )
    (net (code "44") (name "Net-(U5-PA9)") (class "Default")
      (node (ref "C14") (pin "2") (pinfunction "2_2") (pintype "passive"))
      (node (ref "SW1") (pin "3") (pinfunction "3_3") (pintype "passive"))
      (node (ref "SW1") (pin "4") (pinfunction "4_4") (pintype "passive"))
      (node (ref "U5") (pin "30") (pinfunction "PA9_30") (pintype "bidirectional"))
    )
    (net (code "45") (name "Net-(U5-PA11)") (class "Default")
      (node (ref "C15") (pin "2") (pinfunction "2_2") (pintype "passive"))
      (node (ref "SW3") (pin "3") (pinfunction "3_3") (pintype "passive"))
      (node (ref "SW3") (pin "4") (pinfunction "4_4") (pintype "passive"))
      (node (ref "U5") (pin "32") (pinfunction "PA11_32") (pintype "bidirectional"))
    )
    (net (code "46") (name "Net-(U5-PA12)") (class "Default")
      (node (ref "C16") (pin "2") (pinfunction "2_2") (pintype "passive"))
      (node (ref "SW4") (pin "3") (pinfunction "3_3") (pintype "passive"))
      (node (ref "SW4") (pin "4") (pinfunction "4_4") (pintype "passive"))
      (node (ref "U5") (pin "33") (pinfunction "PA12_33") (pintype "bidirectional"))
    )
    (net (code "47") (name "Net-(U5-PA15)") (class "Default")
      (node (ref "C17") (pin "2") (pinfunction "2_2") (pintype "passive"))
      (node (ref "SW5") (pin "3") (pinfunction "3_3") (pintype "passive"))
      (node (ref "SW5") (pin "4") (pinfunction "4_4") (pintype "passive"))
      (node (ref "U5") (pin "38") (pinfunction "PA15_38") (pintype "bidirectional"))
    )
    (net (code "48") (name "Net-(U5-PB6)") (class "Default")
      (node (ref "R19") (pin "2") (pinfunction "2_2") (pintype "passive"))
      (node (ref "U5") (pin "42") (pinfunction "PB6_42") (pintype "bidirectional"))
    )
    (net (code "49") (name "Net-(U5-PD0_OSC_IN)") (class "Default")
      (node (ref "C8") (pin "2") (pinfunction "2_2") (pintype "passive"))
      (node (ref "U5") (pin "5") (pinfunction "PD0_OSC_IN_5") (pintype "bidirectional"))
      (node (ref "X1") (pin "P$2") (pinfunction "3_P$2") (pintype "bidirectional"))
    )
    (net (code "50") (name "Net-(U5-PD1_OSC_OUT)") (class "Default")
      (node (ref "C7") (pin "2") (pinfunction "2_2") (pintype "passive"))
      (node (ref "U5") (pin "6") (pinfunction "PD1_OSC_OUT_6") (pintype "bidirectional"))
      (node (ref "X1") (pin "P$1") (pinfunction "1_P$1") (pintype "bidirectional"))
    )
    (net (code "51") (name "Net-(U6-+IN)") (class "Default")
      (node (ref "R19") (pin "1") (pinfunction "1_1") (pintype "passive"))
      (node (ref "R20") (pin "2") (pinfunction "2_2") (pintype "passive"))
      (node (ref "U6") (pin "1") (pinfunction "+IN_1") (pintype "input"))
    )
    (net (code "52") (name "PeriphPWR") (class "Default")
      (node (ref "C19") (pin "1") (pinfunction "1_1") (pintype "passive"))
      (node (ref "C3") (pin "2") (pinfunction "2_2") (pintype "passive"))
      (node (ref "C4") (pin "2") (pinfunction "2_2") (pintype "passive"))
      (node (ref "C5") (pin "2") (pinfunction "2_2") (pintype "passive"))
      (node (ref "P10") (pin "2") (pinfunction "V3.3_2") (pintype "power_in"))
      (node (ref "P7") (pin "2") (pinfunction "V3.3_2") (pintype "power_in"))
      (node (ref "P8") (pin "2") (pinfunction "V3.3_2") (pintype "power_in"))
      (node (ref "P9") (pin "2") (pinfunction "V3.3_2") (pintype "power_in"))
      (node (ref "Q4") (pin "3") (pinfunction "D_3") (pintype "passive"))
      (node (ref "U2") (pin "4") (pinfunction "VCC+_4") (pintype "power_in"))
      (node (ref "U3") (pin "4") (pinfunction "VCC+_4") (pintype "power_in"))
      (node (ref "U4") (pin "4") (pinfunction "VCC+_4") (pintype "power_in"))
      (node (ref "U6") (pin "5") (pinfunction "V+_5") (pintype "power_in"))
    )
    (net (code "53") (name "SWDCLK") (class "Default")
      (node (ref "P2") (pin "2") (pinfunction "SWDCLK_2") (pintype "bidirectional"))
      (node (ref "U5") (pin "37") (pinfunction "PA14_37") (pintype "bidirectional"))
    )
    (net (code "54") (name "SWDIO") (class "Default")
      (node (ref "P2") (pin "3") (pinfunction "SWDIO_3") (pintype "bidirectional"))
      (node (ref "U5") (pin "34") (pinfunction "PA13_34") (pintype "bidirectional"))
    )
    (net (code "55") (name "V3.3") (class "Default")
      (node (ref "C18") (pin "1") (pinfunction "1_1") (pintype "passive"))
      (node (ref "C2") (pin "2") (pinfunction "2_2") (pintype "passive"))
      (node (ref "C20") (pin "2") (pinfunction "2_2") (pintype "passive"))
      (node (ref "C21") (pin "2") (pinfunction "2_2") (pintype "passive"))
      (node (ref "C22") (pin "2") (pinfunction "2_2") (pintype "passive"))
      (node (ref "D1") (pin "2") (pinfunction "K_2") (pintype "passive"))
      (node (ref "J1") (pin "1") (pinfunction "1_1") (pintype "passive"))
      (node (ref "P2") (pin "4") (pinfunction "+3.3V_4") (pintype "power_in"))
      (node (ref "P3") (pin "2") (pinfunction "Vpp_2") (pintype "power_in"))
      (node (ref "Q5") (pin "2") (pinfunction "S_2") (pintype "passive"))
      (node (ref "R26") (pin "1") (pinfunction "1_1") (pintype "passive"))
      (node (ref "R27") (pin "1") (pinfunction "1_1") (pintype "passive"))
      (node (ref "SW2") (pin "1") (pinfunction "1_1") (pintype "passive"))
      (node (ref "SW2") (pin "2") (pinfunction "2_2") (pintype "passive"))
      (node (ref "U1") (pin "2") (pinfunction "VOUT_2") (pintype "power_in"))
      (node (ref "U5") (pin "24") (pinfunction "VDD_24") (pintype "power_in"))
      (node (ref "U5") (pin "36") (pinfunction "VDD_36") (pintype "power_in"))
      (node (ref "U5") (pin "48") (pinfunction "VDD_48") (pintype "power_in"))
    )
    (net (code "56") (name "VDDA") (class "Default")
      (node (ref "C6") (pin "2") (pinfunction "2_2") (pintype "passive"))
      (node (ref "J1") (pin "2") (pinfunction "2_2") (pintype "passive"))
      (node (ref "Q4") (pin "2") (pinfunction "S_2") (pintype "passive"))
      (node (ref "R25") (pin "1") (pinfunction "1_1") (pintype "passive"))
      (node (ref "U5") (pin "9") (pinfunction "VDDA_9") (pintype "power_in"))
    )
    (net (code "57") (name "Vpp") (class "Default")
      (node (ref "C1") (pin "2") (pinfunction "2_2") (pintype "passive"))
      (node (ref "P1") (pin "2") (pinfunction "Vpp_2") (pintype "power_in"))
      (node (ref "Q3") (pin "2") (pinfunction "S_2") (pintype "passive"))
      (node (ref "R24") (pin "1") (pinfunction "1_1") (pintype "passive"))
      (node (ref "U1") (pin "3") (pinfunction "VIN_3") (pintype "input"))
    )
    (net (code "58") (name "dispPWR") (class "Default")
      (node (ref "P4") (pin "6") (pinfunction "VCC_6") (pintype "power_in"))
      (node (ref "P6") (pin "6") (pinfunction "VCC_6") (pintype "power_in"))
      (node (ref "Q5") (pin "3") (pinfunction "D_3") (pintype "passive"))
    )
    (net (code "59") (name "dispRES") (class "Default")
      (node (ref "P4") (pin "1") (pinfunction "RST_1") (pintype "bidirectional"))
      (node (ref "P6") (pin "1") (pinfunction "RST_1") (pintype "bidirectional"))
      (node (ref "U5") (pin "20") (pinfunction "PB2_20") (pintype "bidirectional"))
    )
    (net (code "60") (name "divbatVolt") (class "Default")
      (node (ref "R21") (pin "1") (pinfunction "1_1") (pintype "passive"))
      (node (ref "R22") (pin "2") (pinfunction "2_2") (pintype "passive"))
      (node (ref "U5") (pin "15") (pinfunction "PA5_15") (pintype "bidirectional"))
    )
    (net (code "61") (name "unconnected-(U5-PA6-Pad16)") (class "Default")
      (node (ref "U5") (pin "16") (pinfunction "PA6_16") (pintype "bidirectional"))
    )
    (net (code "62") (name "unconnected-(U5-PA8-Pad29)") (class "Default")
      (node (ref "U5") (pin "29") (pinfunction "PA8_29") (pintype "bidirectional"))
    )
    (net (code "63") (name "unconnected-(U5-PB7-Pad43)") (class "Default")
      (node (ref "U5") (pin "43") (pinfunction "PB7_43") (pintype "bidirectional"))
    )
    (net (code "64") (name "unconnected-(U5-PB8-Pad45)") (class "Default")
      (node (ref "U5") (pin "45") (pinfunction "PB8_45") (pintype "bidirectional"))
    )
    (net (code "65") (name "unconnected-(U5-PB9-Pad46)") (class "Default")
      (node (ref "U5") (pin "46") (pinfunction "PB9_46") (pintype "bidirectional"))
    )
    (net (code "66") (name "unconnected-(U5-PB11-Pad22)") (class "Default")
      (node (ref "U5") (pin "22") (pinfunction "PB11_22") (pintype "bidirectional"))
    )
    (net (code "67") (name "unconnected-(U5-PB12-Pad25)") (class "Default")
      (node (ref "U5") (pin "25") (pinfunction "PB12_25") (pintype "bidirectional"))
    )
    (net (code "68") (name "unconnected-(U5-PB13-Pad26)") (class "Default")
      (node (ref "U5") (pin "26") (pinfunction "PB13_26") (pintype "bidirectional"))
    )
    (net (code "69") (name "unconnected-(U5-PB14-Pad27)") (class "Default")
      (node (ref "U5") (pin "27") (pinfunction "PB14_27") (pintype "bidirectional"))
    )
    (net (code "70") (name "unconnected-(U5-PB15-Pad28)") (class "Default")
      (node (ref "U5") (pin "28") (pinfunction "PB15_28") (pintype "bidirectional"))
    )
    (net (code "71") (name "unconnected-(U5-PC13-TAMPER-RTC-Pad2)") (class "Default")
      (node (ref "U5") (pin "2") (pinfunction "PC13-TAMPER-RTC_2") (pintype "bidirectional"))
    )
    (net (code "72") (name "unconnected-(U5-PC14-OSC32_IN-Pad3)") (class "Default")
      (node (ref "U5") (pin "3") (pinfunction "PC14-OSC32_IN_3") (pintype "bidirectional"))
    )
    (net (code "73") (name "unconnected-(U5-PC15-OSC32_OUT-Pad4)") (class "Default")
      (node (ref "U5") (pin "4") (pinfunction "PC15-OSC32_OUT_4") (pintype "bidirectional"))
    )
    (net (code "74") (name "unconnected-(U5-VBAT-Pad1)") (class "Default")
      (node (ref "U5") (pin "1") (pinfunction "VBAT_1") (pintype "bidirectional"))
    )
    (net (code "75") (name "virtZero") (class "Default")
      (node (ref "R13") (pin "1") (pinfunction "1_1") (pintype "passive"))
      (node (ref "R14") (pin "1") (pinfunction "1_1") (pintype "passive"))
      (node (ref "R15") (pin "1") (pinfunction "1_1") (pintype "passive"))
      (node (ref "R16") (pin "2") (pinfunction "2_2") (pintype "passive"))
      (node (ref "U5") (pin "14") (pinfunction "PA4_14") (pintype "bidirectional"))
      (node (ref "U6") (pin "3") (pinfunction "-IN_3") (pintype "input"))
      (node (ref "U6") (pin "4") (pinfunction "OUT_4") (pintype "output"))
    )
  )
)
